# MCU.net
KiCad netlist of a schematic drawn in Altium Designer
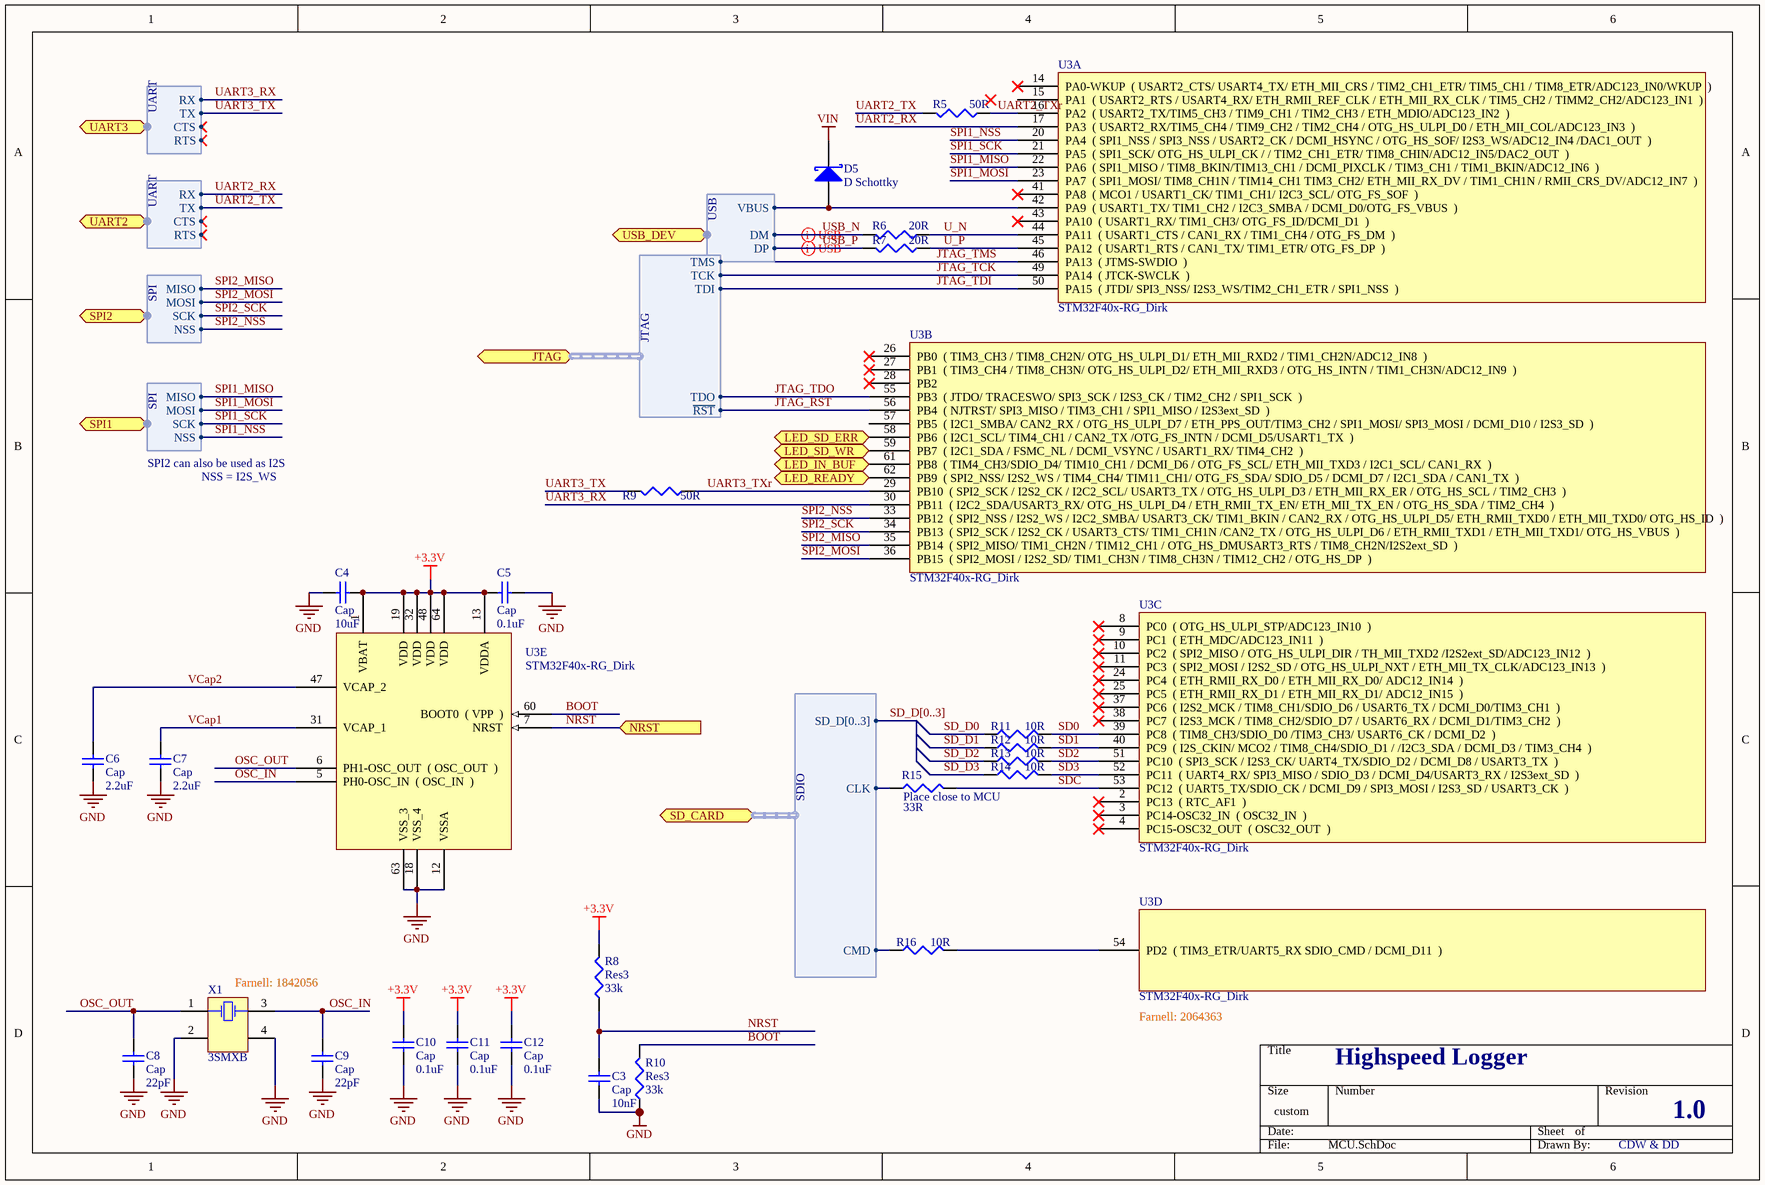
[diagram p0: MCU.SchDoc]

(export (version "E")
  (design (tool "Eeschema 10.0.6"))
  (components
    (comp (ref "C3")
      (value "Cap")
      (footprint "V0402")
      (description "Capacitor")
      (fields (field (name "ALTIUM_VALUE") "10nF") (field (name "PUBLISHER") "Altium Limited"))
      (libsource (lib "altium-import") (part "root_1_Cap_"))
    )
    (comp (ref "C4")
      (value "Cap")
      (footprint "V0603")
      (description "Capacitor")
      (fields (field (name "ALTIUM_VALUE") "10uF") (field (name "PUBLISHER") "Altium Limited"))
      (libsource (lib "Miscellaneous Devices") (part "Cap"))
    )
    (comp (ref "C5")
      (value "Cap")
      (footprint "V0402")
      (description "Capacitor")
      (fields (field (name "ALTIUM_VALUE") "0.1uF") (field (name "PUBLISHER") "Altium Limited"))
      (libsource (lib "Miscellaneous Devices") (part "Cap"))
    )
    (comp (ref "C6")
      (value "Cap")
      (footprint "V0402")
      (description "Capacitor")
      (fields (field (name "ALTIUM_VALUE") "2.2uF") (field (name "PUBLISHER") "Altium Limited"))
      (libsource (lib "Miscellaneous Devices") (part "Cap"))
    )
    (comp (ref "C7")
      (value "Cap")
      (footprint "V0402")
      (description "Capacitor")
      (fields (field (name "ALTIUM_VALUE") "2.2uF") (field (name "PUBLISHER") "Altium Limited"))
      (libsource (lib "Miscellaneous Devices") (part "Cap"))
    )
    (comp (ref "C8")
      (value "Cap")
      (footprint "V0402")
      (description "Capacitor")
      (fields (field (name "ALTIUM_VALUE") "22pF") (field (name "PUBLISHER") "Altium Limited"))
      (libsource (lib "altium-import") (part "root_1_Cap_"))
    )
    (comp (ref "C9")
      (value "Cap")
      (footprint "V0402")
      (description "Capacitor")
      (fields (field (name "ALTIUM_VALUE") "22pF") (field (name "PUBLISHER") "Altium Limited"))
      (libsource (lib "altium-import") (part "root_3_Cap_"))
    )
    (comp (ref "C10")
      (value "Cap")
      (footprint "V0402")
      (description "Capacitor")
      (fields (field (name "ALTIUM_VALUE") "0.1uF") (field (name "PUBLISHER") "Altium Limited"))
      (libsource (lib "Miscellaneous Devices") (part "Cap"))
    )
    (comp (ref "C11")
      (value "Cap")
      (footprint "V0402")
      (description "Capacitor")
      (fields (field (name "ALTIUM_VALUE") "0.1uF") (field (name "PUBLISHER") "Altium Limited"))
      (libsource (lib "Miscellaneous Devices") (part "Cap"))
    )
    (comp (ref "C12")
      (value "Cap")
      (footprint "V0402")
      (description "Capacitor")
      (fields (field (name "ALTIUM_VALUE") "0.1uF") (field (name "PUBLISHER") "Altium Limited"))
      (libsource (lib "Miscellaneous Devices") (part "Cap"))
    )
    (comp (ref "D5")
      (value "D Schottky")
      (footprint "SOD-323")
      (description "Schottky Diode")
      (fields (field (name "PUBLISHER") "Altium Limited"))
      (libsource (lib "Miscellaneous Devices") (part "D Schottky"))
    )
    (comp (ref "R5")
      (value "50R")
      (footprint "V0402RES")
      (description "Resistor")
      (fields (field (name "Comment") "Res3") (field (name "PUBLISHER") "Altium Limited"))
      (libsource (lib "altium-import") (part "root_2_Res3_"))
    )
    (comp (ref "R6")
      (value "20R")
      (footprint "V0402RES")
      (description "Resistor")
      (fields (field (name "Comment") "Res3") (field (name "PUBLISHER") "Altium Limited"))
      (libsource (lib "altium-import") (part "root_2_Res3_"))
    )
    (comp (ref "R7")
      (value "20R")
      (footprint "V0402RES")
      (description "Resistor")
      (fields (field (name "Comment") "Res3") (field (name "PUBLISHER") "Altium Limited"))
      (libsource (lib "altium-import") (part "root_2_Res3_"))
    )
    (comp (ref "R8")
      (value "Res3")
      (footprint "V0402RES")
      (description "Resistor")
      (fields (field (name "ALTIUM_VALUE") "33k") (field (name "PUBLISHER") "Altium Limited"))
      (libsource (lib "altium-import") (part "root_1_Res3_"))
    )
    (comp (ref "R9")
      (value "50R")
      (footprint "V0402RES")
      (description "Resistor")
      (fields (field (name "Comment") "Res3") (field (name "PUBLISHER") "Altium Limited"))
      (libsource (lib "altium-import") (part "root_2_Res3_"))
    )
    (comp (ref "R10")
      (value "Res3")
      (footprint "V0402RES")
      (description "Resistor")
      (fields (field (name "ALTIUM_VALUE") "33k") (field (name "PUBLISHER") "Altium Limited"))
      (libsource (lib "altium-import") (part "root_1_Res3_"))
    )
    (comp (ref "R11")
      (value "10R")
      (footprint "V0402RES")
      (description "Resistor")
      (fields (field (name "Comment") "Place close to MCU") (field (name "PUBLISHER") "Altium Limited"))
      (libsource (lib "altium-import") (part "root_0_Res3_"))
    )
    (comp (ref "R12")
      (value "10R")
      (footprint "V0402RES")
      (description "Resistor")
      (fields (field (name "Comment") "Place close to MCU") (field (name "PUBLISHER") "Altium Limited"))
      (libsource (lib "altium-import") (part "root_0_Res3_"))
    )
    (comp (ref "R13")
      (value "10R")
      (footprint "V0402RES")
      (description "Resistor")
      (fields (field (name "Comment") "Place close to MCU") (field (name "PUBLISHER") "Altium Limited"))
      (libsource (lib "altium-import") (part "root_0_Res3_"))
    )
    (comp (ref "R14")
      (value "10R")
      (footprint "V0402RES")
      (description "Resistor")
      (fields (field (name "Comment") "Place close to MCU") (field (name "PUBLISHER") "Altium Limited"))
      (libsource (lib "altium-import") (part "root_0_Res3_"))
    )
    (comp (ref "R15")
      (value "Place close to MCU")
      (footprint "V0402RES")
      (description "Resistor")
      (fields (field (name "ALTIUM_VALUE") "33R") (field (name "PUBLISHER") "Altium Limited"))
      (libsource (lib "altium-import") (part "root_0_Res3_"))
    )
    (comp (ref "R16")
      (value "10R")
      (footprint "V0402RES")
      (description "Resistor")
      (fields (field (name "Comment") "Place close to MCU") (field (name "PUBLISHER") "Altium Limited"))
      (libsource (lib "altium-import") (part "root_0_Res3_"))
    )
    (comp (ref "U3")
      (value "STM32F40x-RG_Dirk")
      (footprint "LQFP64")
      (fields (field (name "FARNELL") "2064363"))
      (libsource (lib "STM32F40X") (part "STM32F40x-RG_Dirk"))
    )
    (comp (ref "X1")
      (value "3SMXB")
      (footprint "CFPX-5")
      (description "Surface Mount Quartz Crystal")
      (fields (field (name "FARNELL") "1842056") (field (name "PUBLISHER") "Altium Limited"))
      (libsource (lib "C-MAC Crystal Oscillator") (part "3SMXB"))
    )
  )
  (nets
    (net (code "6") (name "+3.3V") (class "Default")
      (node (ref "C10") (pin "2") (pinfunction "2_2") (pintype "passive"))
      (node (ref "C11") (pin "2") (pinfunction "2_2") (pintype "passive"))
      (node (ref "C12") (pin "2") (pinfunction "2_2") (pintype "passive"))
      (node (ref "C4") (pin "1") (pinfunction "1_1") (pintype "passive"))
      (node (ref "C5") (pin "2") (pinfunction "2_2") (pintype "passive"))
      (node (ref "R8") (pin "2") (pinfunction "2_2") (pintype "passive"))
      (node (ref "U3") (pin "1") (pinfunction "VBAT_1") (pintype "power_in"))
      (node (ref "U3") (pin "13") (pinfunction "VDDA_13") (pintype "power_in"))
      (node (ref "U3") (pin "19") (pinfunction "VDD_19") (pintype "power_in"))
      (node (ref "U3") (pin "32") (pinfunction "VDD_32") (pintype "power_in"))
      (node (ref "U3") (pin "48") (pinfunction "VDD_48") (pintype "power_in"))
      (node (ref "U3") (pin "64") (pinfunction "VDD_64") (pintype "power_in"))
    )
    (net (code "7") (name "/BOOT") (class "Default")
      (node (ref "R10") (pin "2") (pinfunction "2_2") (pintype "passive"))
      (node (ref "U3") (pin "60") (pinfunction "BOOT0__(_VPP__)_60") (pintype "input"))
    )
    (net (code "8") (name "/CLK") (class "Default")
      (node (ref "R15") (pin "1") (pinfunction "1_1") (pintype "passive"))
    )
    (net (code "9") (name "/CMD") (class "Default")
      (node (ref "R16") (pin "1") (pinfunction "1_1") (pintype "passive"))
    )
    (net (code "10") (name "/JTAG_RST") (class "Default")
      (node (ref "U3") (pin "56") (pinfunction "PB4__(_NJTRST/_SPI3_MISO_/_TIM3_CH1_/_SPI1_MISO_/_I2S3ext_SD__)_56") (pintype "passive"))
    )
    (net (code "11") (name "/JTAG_TCK") (class "Default")
      (node (ref "U3") (pin "49") (pinfunction "PA14__(_JTCK-SWCLK__)_49") (pintype "passive"))
    )
    (net (code "12") (name "/JTAG_TDI") (class "Default")
      (node (ref "U3") (pin "50") (pinfunction "PA15__(_JTDI/_SPI3_NSS/_I2S3_WS/TIM2_CH1_ETR_/_SPI1_NSS__)_50") (pintype "passive"))
    )
    (net (code "13") (name "/JTAG_TDO") (class "Default")
      (node (ref "U3") (pin "55") (pinfunction "PB3__(_JTDO/_TRACESWO/_SPI3_SCK_/_I2S3_CK_/_TIM2_CH2_/_SPI1_SCK__)_55") (pintype "passive"))
    )
    (net (code "14") (name "/JTAG_TMS") (class "Default")
      (node (ref "U3") (pin "46") (pinfunction "PA13__(_JTMS-SWDIO__)_46") (pintype "passive"))
    )
    (net (code "15") (name "/LED_IN_BUF") (class "Default")
      (node (ref "U3") (pin "61") (pinfunction "PB8__(_TIM4_CH3/SDIO_D4/_TIM10_CH1_/_DCMI_D6_/_OTG_FS_SCL/_ETH_MII_TXD3_/_I2C1_SCL/_CAN1_RX__)_61") (pintype "passive"))
    )
    (net (code "16") (name "/LED_READY") (class "Default")
      (node (ref "U3") (pin "62") (pinfunction "PB9__(_SPI2_NSS/_I2S2_WS_/_TIM4_CH4/_TIM11_CH1/_OTG_FS_SDA/_SDIO_D5_/_DCMI_D7_/_I2C1_SDA_/_CAN1_TX__)_62") (pintype "passive"))
    )
    (net (code "17") (name "/LED_SD_ERR") (class "Default")
      (node (ref "U3") (pin "58") (pinfunction "PB6__(_I2C1_SCL/_TIM4_CH1_/_CAN2_TX_/OTG_FS_INTN_/_DCMI_D5/USART1_TX__)_58") (pintype "passive"))
    )
    (net (code "18") (name "/LED_SD_WR") (class "Default")
      (node (ref "U3") (pin "59") (pinfunction "PB7__(_I2C1_SDA_/_FSMC_NL_/_DCMI_VSYNC_/_USART1_RX/_TIM4_CH2__)_59") (pintype "passive"))
    )
    (net (code "19") (name "/NRST") (class "Default")
      (node (ref "C3") (pin "2") (pinfunction "2_2") (pintype "passive"))
      (node (ref "R8") (pin "1") (pinfunction "1_1") (pintype "passive"))
      (node (ref "U3") (pin "7") (pinfunction "NRST_7") (pintype "input"))
    )
    (net (code "20") (name "/OSC_IN") (class "Default")
      (node (ref "C9") (pin "1") (pinfunction "1_1") (pintype "passive"))
      (node (ref "U3") (pin "5") (pinfunction "PH0-OSC_IN__(_OSC_IN__)_5") (pintype "passive"))
      (node (ref "X1") (pin "3") (pinfunction "OSC2_3") (pintype "passive"))
    )
    (net (code "21") (name "/OSC_OUT") (class "Default")
      (node (ref "C8") (pin "2") (pinfunction "2_2") (pintype "passive"))
      (node (ref "U3") (pin "6") (pinfunction "PH1-OSC_OUT__(_OSC_OUT__)_6") (pintype "passive"))
      (node (ref "X1") (pin "1") (pinfunction "OSC1_1") (pintype "passive"))
    )
    (net (code "22") (name "/SD0") (class "Default")
      (node (ref "R11") (pin "2") (pinfunction "2_2") (pintype "passive"))
      (node (ref "U3") (pin "39") (pinfunction "PC8__(_TIM8_CH3/SDIO_D0_/TIM3_CH3/_USART6_CK_/_DCMI_D2__)_39") (pintype "passive"))
    )
    (net (code "23") (name "/SD1") (class "Default")
      (node (ref "R12") (pin "2") (pinfunction "2_2") (pintype "passive"))
      (node (ref "U3") (pin "40") (pinfunction "PC9__(_I2S_CKIN/_MCO2_/_TIM8_CH4/SDIO_D1_/_/I2C3_SDA_/_DCMI_D3_/_TIM3_CH4__)_40") (pintype "passive"))
    )
    (net (code "24") (name "/SD2") (class "Default")
      (node (ref "R13") (pin "2") (pinfunction "2_2") (pintype "passive"))
      (node (ref "U3") (pin "51") (pinfunction "PC10__(_SPI3_SCK_/_I2S3_CK/_UART4_TX/SDIO_D2_/_DCMI_D8_/_USART3_TX__)_51") (pintype "passive"))
    )
    (net (code "25") (name "/SD3") (class "Default")
      (node (ref "R14") (pin "2") (pinfunction "2_2") (pintype "passive"))
      (node (ref "U3") (pin "52") (pinfunction "PC11__(_UART4_RX/_SPI3_MISO_/_SDIO_D3_/_DCMI_D4/USART3_RX_/_I2S3ext_SD__)_52") (pintype "passive"))
    )
    (net (code "26") (name "/SDC") (class "Default")
      (node (ref "R15") (pin "2") (pinfunction "2_2") (pintype "passive"))
      (node (ref "U3") (pin "53") (pinfunction "PC12__(_UART5_TX/SDIO_CK_/_DCMI_D9_/_SPI3_MOSI_/_I2S3_SD_/_USART3_CK__)_53") (pintype "passive"))
    )
    (net (code "27") (name "/SD_D0") (class "Default")
      (node (ref "R11") (pin "1") (pinfunction "1_1") (pintype "passive"))
    )
    (net (code "28") (name "/SD_D1") (class "Default")
      (node (ref "R12") (pin "1") (pinfunction "1_1") (pintype "passive"))
    )
    (net (code "29") (name "/SD_D2") (class "Default")
      (node (ref "R13") (pin "1") (pinfunction "1_1") (pintype "passive"))
    )
    (net (code "30") (name "/SD_D3") (class "Default")
      (node (ref "R14") (pin "1") (pinfunction "1_1") (pintype "passive"))
    )
    (net (code "32") (name "/SPI1_MISO") (class "Default")
      (node (ref "U3") (pin "22") (pinfunction "PA6__(_SPI1_MISO_/_TIM8_BKIN/TIM13_CH1_/_DCMI_PIXCLK_/_TIM3_CH1_/_TIM1_BKIN/ADC12_IN6__)_22") (pintype "passive"))
    )
    (net (code "33") (name "/SPI1_MOSI") (class "Default")
      (node (ref "U3") (pin "23") (pinfunction "PA7__(_SPI1_MOSI/_TIM8_CH1N_/_TIM14_CH1_TIM3_CH2/_ETH_MII_RX_DV_/_TIM1_CH1N_/_RMII_CRS_DV/ADC12_IN7__)_23") (pintype "passive"))
    )
    (net (code "34") (name "/SPI1_NSS") (class "Default")
      (node (ref "U3") (pin "20") (pinfunction "PA4__(_SPI1_NSS_/_SPI3_NSS_/_USART2_CK_/_DCMI_HSYNC_/_OTG_HS_SOF/_I2S3_WS/ADC12_IN4_/DAC1_OUT__)_20") (pintype "passive"))
    )
    (net (code "35") (name "/SPI1_SCK") (class "Default")
      (node (ref "U3") (pin "21") (pinfunction "PA5__(_SPI1_SCK/_OTG_HS_ULPI_CK_/_/_TIM2_CH1_ETR/_TIM8_CHIN/ADC12_IN5/DAC2_OUT__)_21") (pintype "passive"))
    )
    (net (code "36") (name "/SPI2_MISO") (class "Default")
      (node (ref "U3") (pin "35") (pinfunction "PB14__(_SPI2_MISO/_TIM1_CH2N_/_TIM12_CH1_/_OTG_HS_DMUSART3_RTS_/_TIM8_CH2N/I2S2ext_SD__)_35") (pintype "passive"))
    )
    (net (code "37") (name "/SPI2_MOSI") (class "Default")
      (node (ref "U3") (pin "36") (pinfunction "PB15__(_SPI2_MOSI_/_I2S2_SD/_TIM1_CH3N_/_TIM8_CH3N_/_TIM12_CH2_/_OTG_HS_DP__)_36") (pintype "passive"))
    )
    (net (code "38") (name "/SPI2_NSS") (class "Default")
      (node (ref "U3") (pin "33") (pinfunction "PB12__(_SPI2_NSS_/_I2S2_WS_/_I2C2_SMBA/_USART3_CK/_TIM1_BKIN_/_CAN2_RX_/_OTG_HS_ULPI_D5/_ETH_RMII_TXD0_/_ETH_MII_TXD0/_OTG_HS_ID__)_33") (pintype "passive"))
    )
    (net (code "39") (name "/SPI2_SCK") (class "Default")
      (node (ref "U3") (pin "34") (pinfunction "PB13__(_SPI2_SCK_/_I2S2_CK_/_USART3_CTS/_TIM1_CH1N_/CAN2_TX_/_OTG_HS_ULPI_D6_/_ETH_RMII_TXD1_/_ETH_MII_TXD1/_OTG_HS_VBUS__)_34") (pintype "passive"))
    )
    (net (code "40") (name "/UART2_RX") (class "Default")
      (node (ref "U3") (pin "17") (pinfunction "PA3__(_USART2_RX/TIM5_CH4_/_TIM9_CH2_/_TIM2_CH4_/_OTG_HS_ULPI_D0_/_ETH_MII_COL/ADC123_IN3__)_17") (pintype "passive"))
    )
    (net (code "41") (name "/UART2_TX") (class "Default")
      (node (ref "R5") (pin "2") (pinfunction "2_2") (pintype "passive"))
    )
    (net (code "42") (name "/UART2_TXr") (class "Default")
      (node (ref "R5") (pin "1") (pinfunction "1_1") (pintype "passive"))
      (node (ref "U3") (pin "16") (pinfunction "PA2__(_USART2_TX/TIM5_CH3_/_TIM9_CH1_/_TIM2_CH3_/_ETH_MDIO/ADC123_IN2__)_16") (pintype "passive"))
    )
    (net (code "43") (name "/UART3_RX") (class "Default")
      (node (ref "U3") (pin "30") (pinfunction "PB11__(_I2C2_SDA/USART3_RX/_OTG_HS_ULPI_D4_/_ETH_RMII_TX_EN/_ETH_MII_TX_EN_/_OTG_HS_SDA_/_TIM2_CH4__)_30") (pintype "passive"))
    )
    (net (code "44") (name "/UART3_TX") (class "Default")
      (node (ref "R9") (pin "2") (pinfunction "2_2") (pintype "passive"))
    )
    (net (code "45") (name "/UART3_TXr") (class "Default")
      (node (ref "R9") (pin "1") (pinfunction "1_1") (pintype "passive"))
      (node (ref "U3") (pin "29") (pinfunction "PB10__(_SPI2_SCK_/_I2S2_CK_/_I2C2_SCL/_USART3_TX_/_OTG_HS_ULPI_D3_/_ETH_MII_RX_ER_/_OTG_HS_SCL_/_TIM2_CH3__)_29") (pintype "passive"))
    )
    (net (code "46") (name "/USB_N") (class "Default")
      (node (ref "R6") (pin "2") (pinfunction "2_2") (pintype "passive"))
    )
    (net (code "47") (name "/USB_P") (class "Default")
      (node (ref "R7") (pin "2") (pinfunction "2_2") (pintype "passive"))
    )
    (net (code "48") (name "/U_N") (class "Default")
      (node (ref "R6") (pin "1") (pinfunction "1_1") (pintype "passive"))
      (node (ref "U3") (pin "44") (pinfunction "PA11__(_USART1_CTS_/_CAN1_RX_/_TIM1_CH4_/_OTG_FS_DM__)_44") (pintype "passive"))
    )
    (net (code "49") (name "/U_P") (class "Default")
      (node (ref "R7") (pin "1") (pinfunction "1_1") (pintype "passive"))
      (node (ref "U3") (pin "45") (pinfunction "PA12__(_USART1_RTS_/_CAN1_TX/_TIM1_ETR/_OTG_FS_DP__)_45") (pintype "passive"))
    )
    (net (code "50") (name "/VBUS") (class "Default")
      (node (ref "D5") (pin "1") (pinfunction "A_1") (pintype "passive"))
      (node (ref "U3") (pin "42") (pinfunction "PA9__(_USART1_TX/_TIM1_CH2_/_I2C3_SMBA_/_DCMI_D0/OTG_FS_VBUS__)_42") (pintype "passive"))
    )
    (net (code "51") (name "/VCap1") (class "Default")
      (node (ref "C7") (pin "2") (pinfunction "2_2") (pintype "passive"))
      (node (ref "U3") (pin "31") (pinfunction "VCAP_1_31") (pintype "passive"))
    )
    (net (code "52") (name "/VCap2") (class "Default")
      (node (ref "C6") (pin "2") (pinfunction "2_2") (pintype "passive"))
      (node (ref "U3") (pin "47") (pinfunction "VCAP_2_47") (pintype "passive"))
    )
    (net (code "58") (name "GND") (class "Default")
      (node (ref "C10") (pin "1") (pinfunction "1_1") (pintype "passive"))
      (node (ref "C11") (pin "1") (pinfunction "1_1") (pintype "passive"))
      (node (ref "C12") (pin "1") (pinfunction "1_1") (pintype "passive"))
      (node (ref "C3") (pin "1") (pinfunction "1_1") (pintype "passive"))
      (node (ref "C4") (pin "2") (pinfunction "2_2") (pintype "passive"))
      (node (ref "C5") (pin "1") (pinfunction "1_1") (pintype "passive"))
      (node (ref "C6") (pin "1") (pinfunction "1_1") (pintype "passive"))
      (node (ref "C7") (pin "1") (pinfunction "1_1") (pintype "passive"))
      (node (ref "C8") (pin "1") (pinfunction "1_1") (pintype "passive"))
      (node (ref "C9") (pin "2") (pinfunction "2_2") (pintype "passive"))
      (node (ref "R10") (pin "1") (pinfunction "1_1") (pintype "passive"))
      (node (ref "U3") (pin "12") (pinfunction "VSSA_12") (pintype "power_in"))
      (node (ref "U3") (pin "18") (pinfunction "VSS_4_18") (pintype "power_in"))
      (node (ref "U3") (pin "63") (pinfunction "VSS_3_63") (pintype "power_in"))
      (node (ref "X1") (pin "2") (pinfunction "NC_2") (pintype "passive"))
      (node (ref "X1") (pin "4") (pinfunction "NC_4") (pintype "passive"))
    )
    (net (code "59") (name "Net-(U3D-PD2__(_TIM3_ETR{slash}UART5_RX_SDIO_CMD_{slash}_DCMI_D11__))") (class "Default")
      (node (ref "R16") (pin "2") (pinfunction "2_2") (pintype "passive"))
      (node (ref "U3") (pin "54") (pinfunction "PD2__(_TIM3_ETR/UART5_RX_SDIO_CMD_/_DCMI_D11__)_54") (pintype "passive"))
    )
    (net (code "60") (name "VIN") (class "Default")
      (node (ref "D5") (pin "2") (pinfunction "K_2") (pintype "passive"))
    )
    (net (code "61") (name "unconnected-(U3A-PA0-WKUP__(_USART2_CTS{slash}_USART4_TX{slash}_ETH_MII_CRS_{slash}_TIM2_CH1_ETR{slash}_TIM5_CH1_{slash}_TIM8_ETR{slash}ADC123_IN0{slash}WKUP__)-Pad14)") (class "Default")
      (node (ref "U3") (pin "14") (pinfunction "PA0-WKUP__(_USART2_CTS/_USART4_TX/_ETH_MII_CRS_/_TIM2_CH1_ETR/_TIM5_CH1_/_TIM8_ETR/ADC123_IN0/WKUP__)_14") (pintype "passive+no_connect"))
    )
    (net (code "62") (name "unconnected-(U3A-PA1__(_USART2_RTS_{slash}_USART4_RX{slash}_ETH_RMII_REF_CLK_{slash}_ETH_MII_RX_CLK_{slash}_TIM5_CH2_{slash}_TIMM2_CH2{slash}ADC123_IN1__)-Pad15)") (class "Default")
      (node (ref "U3") (pin "15") (pinfunction "PA1__(_USART2_RTS_/_USART4_RX/_ETH_RMII_REF_CLK_/_ETH_MII_RX_CLK_/_TIM5_CH2_/_TIMM2_CH2/ADC123_IN1__)_15") (pintype "passive"))
    )
    (net (code "63") (name "unconnected-(U3A-PA8__(_MCO1_{slash}_USART1_CK{slash}_TIM1_CH1{slash}_I2C3_SCL{slash}_OTG_FS_SOF__)-Pad41)") (class "Default")
      (node (ref "U3") (pin "41") (pinfunction "PA8__(_MCO1_/_USART1_CK/_TIM1_CH1/_I2C3_SCL/_OTG_FS_SOF__)_41") (pintype "passive+no_connect"))
    )
    (net (code "64") (name "unconnected-(U3A-PA10__(_USART1_RX{slash}_TIM1_CH3{slash}_OTG_FS_ID{slash}DCMI_D1__)-Pad43)") (class "Default")
      (node (ref "U3") (pin "43") (pinfunction "PA10__(_USART1_RX/_TIM1_CH3/_OTG_FS_ID/DCMI_D1__)_43") (pintype "passive+no_connect"))
    )
    (net (code "65") (name "unconnected-(U3B-PB0__(_TIM3_CH3_{slash}_TIM8_CH2N{slash}_OTG_HS_ULPI_D1{slash}_ETH_MII_RXD2_{slash}_TIM1_CH2N{slash}ADC12_IN8__)-Pad26)") (class "Default")
      (node (ref "U3") (pin "26") (pinfunction "PB0__(_TIM3_CH3_/_TIM8_CH2N/_OTG_HS_ULPI_D1/_ETH_MII_RXD2_/_TIM1_CH2N/ADC12_IN8__)_26") (pintype "passive+no_connect"))
    )
    (net (code "66") (name "unconnected-(U3B-PB1__(_TIM3_CH4_{slash}_TIM8_CH3N{slash}_OTG_HS_ULPI_D2{slash}_ETH_MII_RXD3_{slash}_OTG_HS_INTN_{slash}_TIM1_CH3N{slash}ADC12_IN9__)-Pad27)") (class "Default")
      (node (ref "U3") (pin "27") (pinfunction "PB1__(_TIM3_CH4_/_TIM8_CH3N/_OTG_HS_ULPI_D2/_ETH_MII_RXD3_/_OTG_HS_INTN_/_TIM1_CH3N/ADC12_IN9__)_27") (pintype "passive+no_connect"))
    )
    (net (code "67") (name "unconnected-(U3B-PB2-Pad28)") (class "Default")
      (node (ref "U3") (pin "28") (pinfunction "PB2_28") (pintype "passive+no_connect"))
    )
    (net (code "68") (name "unconnected-(U3B-PB5__(_I2C1_SMBA{slash}_CAN2_RX_{slash}_OTG_HS_ULPI_D7_{slash}_ETH_PPS_OUT{slash}TIM3_CH2_{slash}_SPI1_MOSI{slash}_SPI3_MOSI_{slash}_DCMI_D10_{slash}_I2S3_SD__)-Pad57)") (class "Default")
      (node (ref "U3") (pin "57") (pinfunction "PB5__(_I2C1_SMBA/_CAN2_RX_/_OTG_HS_ULPI_D7_/_ETH_PPS_OUT/TIM3_CH2_/_SPI1_MOSI/_SPI3_MOSI_/_DCMI_D10_/_I2S3_SD__)_57") (pintype "passive"))
    )
    (net (code "69") (name "unconnected-(U3C-PC0__(_OTG_HS_ULPI_STP{slash}ADC123_IN10__)-Pad8)") (class "Default")
      (node (ref "U3") (pin "8") (pinfunction "PC0__(_OTG_HS_ULPI_STP/ADC123_IN10__)_8") (pintype "passive+no_connect"))
    )
    (net (code "70") (name "unconnected-(U3C-PC1__(_ETH_MDC{slash}ADC123_IN11__)-Pad9)") (class "Default")
      (node (ref "U3") (pin "9") (pinfunction "PC1__(_ETH_MDC/ADC123_IN11__)_9") (pintype "passive+no_connect"))
    )
    (net (code "71") (name "unconnected-(U3C-PC2__(_SPI2_MISO_{slash}_OTG_HS_ULPI_DIR_{slash}_TH_MII_TXD2_{slash}I2S2ext_SD{slash}ADC123_IN12__)-Pad10)") (class "Default")
      (node (ref "U3") (pin "10") (pinfunction "PC2__(_SPI2_MISO_/_OTG_HS_ULPI_DIR_/_TH_MII_TXD2_/I2S2ext_SD/ADC123_IN12__)_10") (pintype "passive+no_connect"))
    )
    (net (code "72") (name "unconnected-(U3C-PC3__(_SPI2_MOSI_{slash}_I2S2_SD_{slash}_OTG_HS_ULPI_NXT_{slash}_ETH_MII_TX_CLK{slash}ADC123_IN13__)-Pad11)") (class "Default")
      (node (ref "U3") (pin "11") (pinfunction "PC3__(_SPI2_MOSI_/_I2S2_SD_/_OTG_HS_ULPI_NXT_/_ETH_MII_TX_CLK/ADC123_IN13__)_11") (pintype "passive+no_connect"))
    )
    (net (code "73") (name "unconnected-(U3C-PC4__(_ETH_RMII_RX_D0_{slash}_ETH_MII_RX_D0{slash}_ADC12_IN14__)-Pad24)") (class "Default")
      (node (ref "U3") (pin "24") (pinfunction "PC4__(_ETH_RMII_RX_D0_/_ETH_MII_RX_D0/_ADC12_IN14__)_24") (pintype "passive+no_connect"))
    )
    (net (code "74") (name "unconnected-(U3C-PC5__(_ETH_RMII_RX_D1_{slash}_ETH_MII_RX_D1{slash}_ADC12_IN15__)-Pad25)") (class "Default")
      (node (ref "U3") (pin "25") (pinfunction "PC5__(_ETH_RMII_RX_D1_/_ETH_MII_RX_D1/_ADC12_IN15__)_25") (pintype "passive+no_connect"))
    )
    (net (code "75") (name "unconnected-(U3C-PC6__(_I2S2_MCK_{slash}_TIM8_CH1{slash}SDIO_D6_{slash}_USART6_TX_{slash}_DCMI_D0{slash}TIM3_CH1__)-Pad37)") (class "Default")
      (node (ref "U3") (pin "37") (pinfunction "PC6__(_I2S2_MCK_/_TIM8_CH1/SDIO_D6_/_USART6_TX_/_DCMI_D0/TIM3_CH1__)_37") (pintype "passive+no_connect"))
    )
    (net (code "76") (name "unconnected-(U3C-PC7__(_I2S3_MCK_{slash}_TIM8_CH2{slash}SDIO_D7_{slash}_USART6_RX_{slash}_DCMI_D1{slash}TIM3_CH2__)-Pad38)") (class "Default")
      (node (ref "U3") (pin "38") (pinfunction "PC7__(_I2S3_MCK_/_TIM8_CH2/SDIO_D7_/_USART6_RX_/_DCMI_D1/TIM3_CH2__)_38") (pintype "passive+no_connect"))
    )
    (net (code "77") (name "unconnected-(U3C-PC13__(_RTC_AF1__)-Pad2)") (class "Default")
      (node (ref "U3") (pin "2") (pinfunction "PC13__(_RTC_AF1__)_2") (pintype "passive+no_connect"))
    )
    (net (code "78") (name "unconnected-(U3C-PC14-OSC32_IN__(_OSC32_IN__)-Pad3)") (class "Default")
      (node (ref "U3") (pin "3") (pinfunction "PC14-OSC32_IN__(_OSC32_IN__)_3") (pintype "passive+no_connect"))
    )
    (net (code "79") (name "unconnected-(U3C-PC15-OSC32_OUT__(_OSC32_OUT__)-Pad4)") (class "Default")
      (node (ref "U3") (pin "4") (pinfunction "PC15-OSC32_OUT__(_OSC32_OUT__)_4") (pintype "passive+no_connect"))
    )
  )
)
